# Headers.net
KiCad netlist of a schematic drawn in Altium Designer
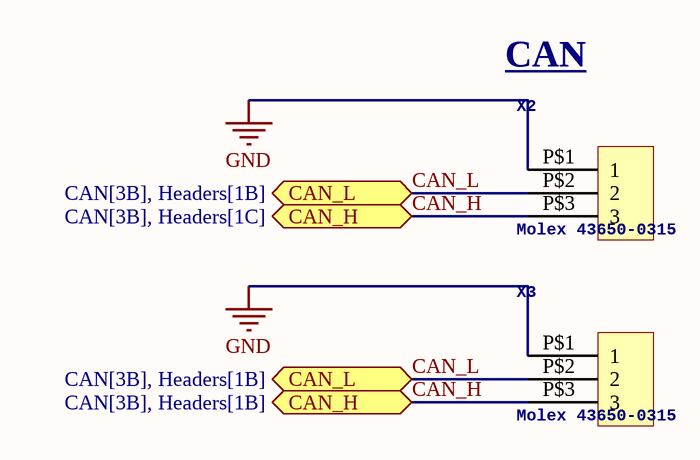
[diagram p0: Headers.SchDoc]

(export (version "E")
  (design (tool "Eeschema 10.0.6"))
  (components
    (comp (ref "X2")
      (value "Molex 43650-0315")
      (footprint "43650-0315")
      (libsource (lib "Molex Microfit") (part "Micro-Fit Molex 3 Pin Vertical"))
    )
    (comp (ref "X3")
      (value "Molex 43650-0315")
      (footprint "43650-0315")
      (libsource (lib "Molex Microfit") (part "Micro-Fit Molex 3 Pin Vertical"))
    )
  )
  (nets
    (net (code "1") (name "/CAN_H") (class "Default")
      (node (ref "X2") (pin "P$3") (pinfunction "3_P$3") (pintype "passive"))
      (node (ref "X3") (pin "P$3") (pinfunction "3_P$3") (pintype "passive"))
    )
    (net (code "2") (name "/CAN_L") (class "Default")
      (node (ref "X2") (pin "P$2") (pinfunction "2_P$2") (pintype "passive"))
      (node (ref "X3") (pin "P$2") (pinfunction "2_P$2") (pintype "passive"))
    )
    (net (code "3") (name "GND") (class "Default")
      (node (ref "X2") (pin "P$1") (pinfunction "1_P$1") (pintype "passive"))
      (node (ref "X3") (pin "P$1") (pinfunction "1_P$1") (pintype "passive"))
    )
  )
)
